# 02_PAB.net
KiCad netlist of a schematic drawn in Altium Designer
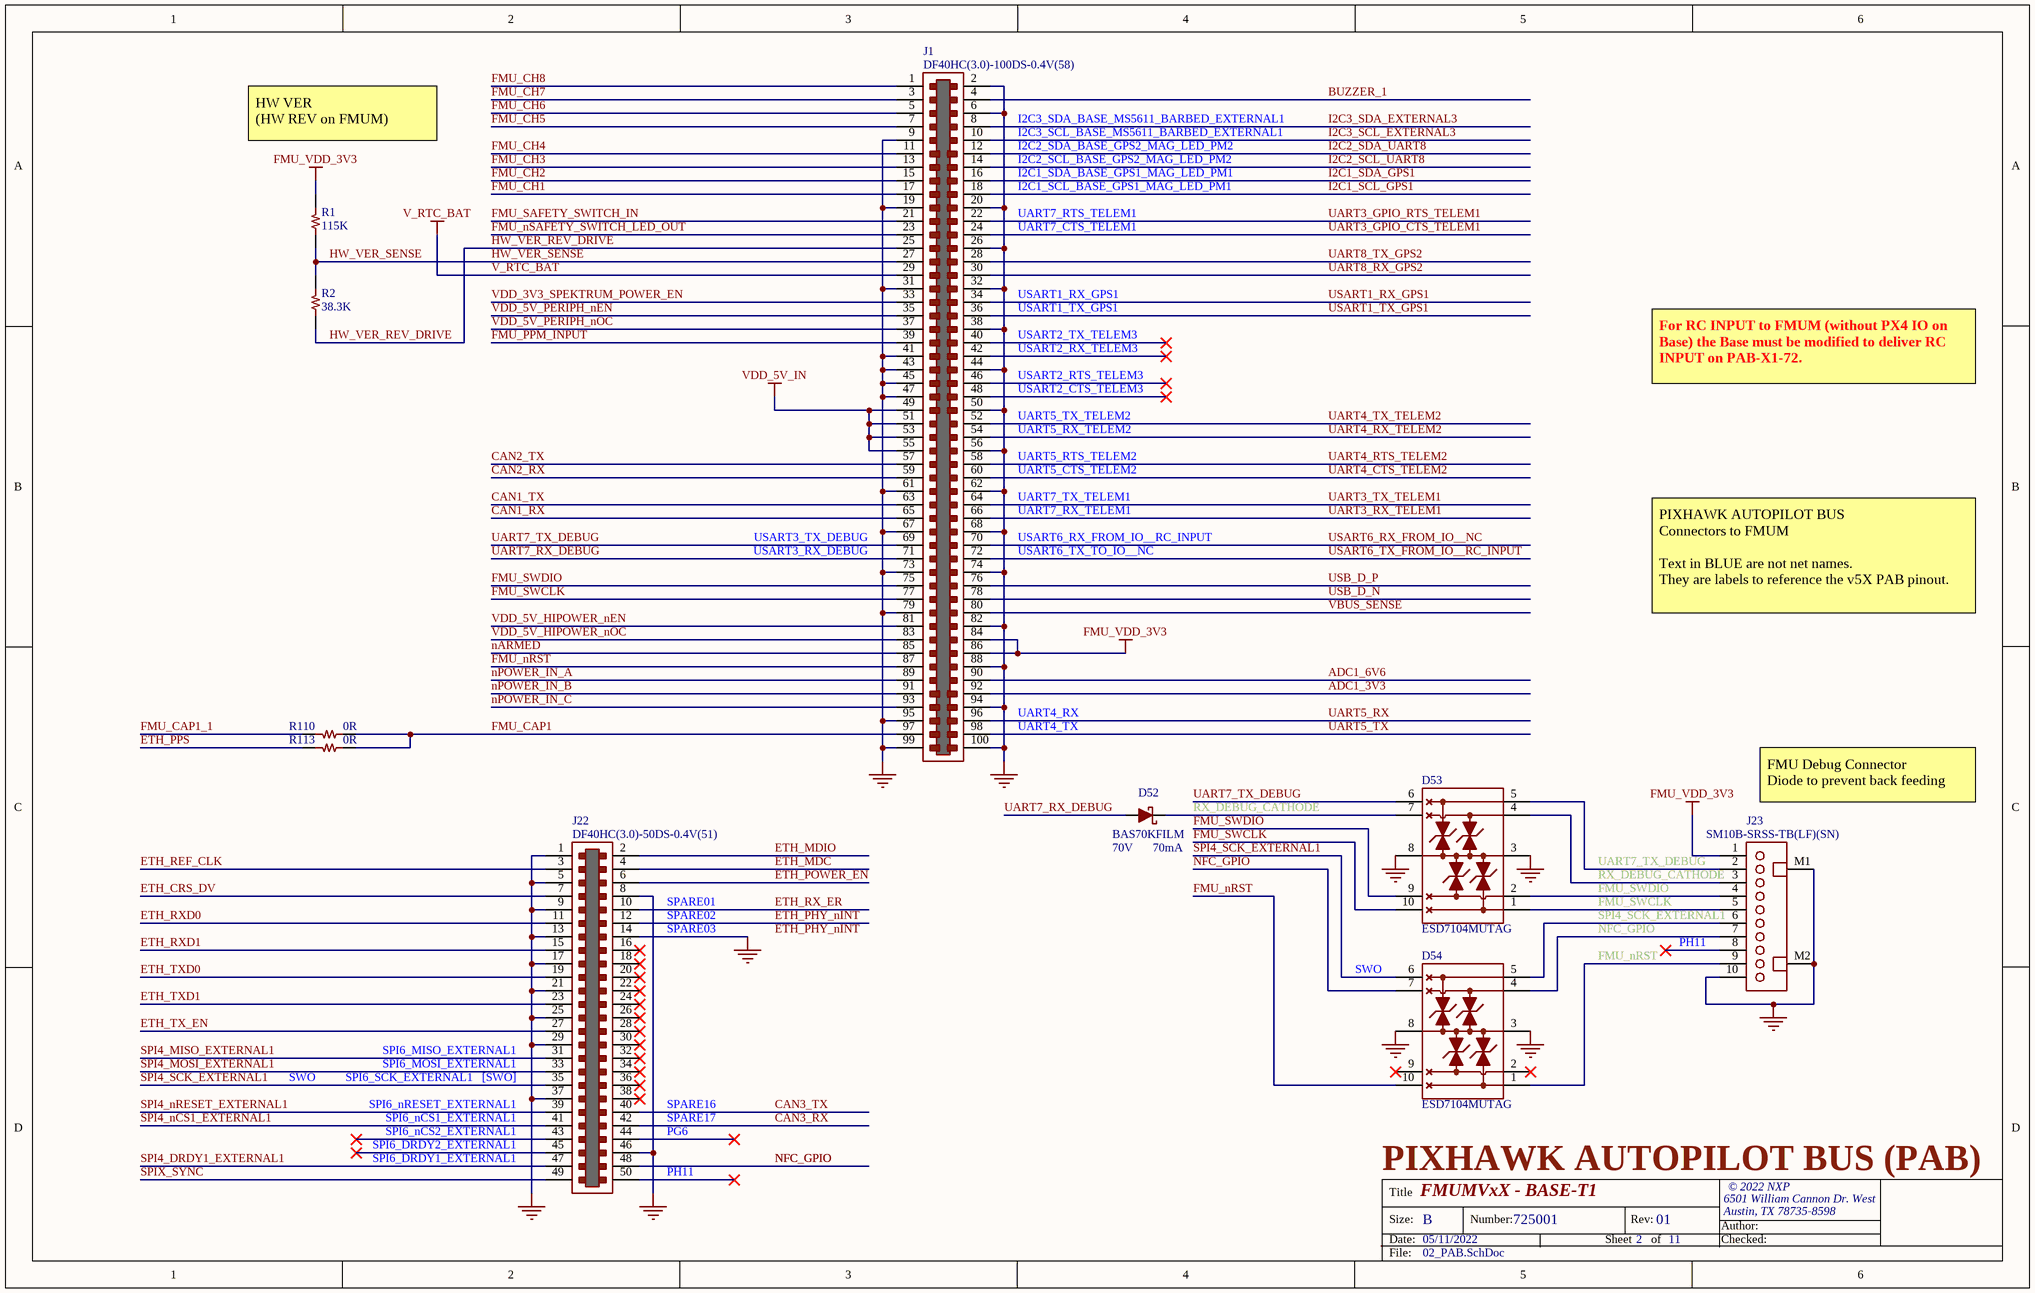
[diagram p0: 02_PAB.SchDoc]

(export (version "E")
  (design (tool "Eeschema 10.0.6"))
  (components
    (comp (ref "D52")
      (value "DIODE SCHOTTKY 70V 70MA SOD523")
      (footprint "SODFL120X80X70L30X30")
      (fields
        (field (name "MANUFACTURER") "STMicroelectronics")
        (field (name "MANUFACTURER PART NUMBER") "BAS70KFILM")
        (field (name "CURRENT") "70mA")
        (field (name "VOLTAGE") "70V")
      )
      (libsource (lib "NscDG_Integrated_Library") (part "DIODE_SCHOTTKY_BAS70_SOD523_SMT"))
    )
    (comp (ref "D53")
      (value "DIODE TVS BIDIRECTIONAL 5V 10V 10UDFN")
      (footprint "UDFN10P50_250X100X55L35X20N")
      (fields
        (field (name "MANUFACTURER") "ON Semiconductor")
        (field (name "MANUFACTURER PART NUMBER") "ESD7104MUTAG")
      )
      (libsource (lib "NscDG_Integrated_Library") (part "DIODE_TVS_4X_10UDFN"))
    )
    (comp (ref "D54")
      (value "DIODE TVS BIDIRECTIONAL 5V 10V 10UDFN")
      (footprint "UDFN10P50_250X100X55L35X20N")
      (fields
        (field (name "MANUFACTURER") "ON Semiconductor")
        (field (name "MANUFACTURER PART NUMBER") "ESD7104MUTAG")
      )
      (libsource (lib "NscDG_Integrated_Library") (part "DIODE_TVS_4X_10UDFN"))
    )
    (comp (ref "J1")
      (value "CONN RCPT 100POS 0.4MM SMD GOLD")
      (footprint "HIROSE_DF40HC3_0-100DS-0_4V51")
      (fields
        (field (name "MANUFACTURER") "Hirose Electric Co Ltd")
        (field (name "MANUFACTURER PART NUMBER") "DF40HC(3.0)-100DS-0.4V(58)")
      )
      (libsource (lib "NscDG_Integrated_Library") (part "CONN_RCPT_2X50_RECPT_0.4MM_SMD"))
    )
    (comp (ref "J22")
      (value "CONN RCPT 50POS 0.4MM SMD GOLD")
      (footprint "HIROSE_DF40C-50DS-0-4V51")
      (fields
        (field (name "MANUFACTURER") "Hirose Electric Co Ltd")
        (field (name "MANUFACTURER PART NUMBER") "DF40HC(3.0)-50DS-0.4V(51)")
      )
      (libsource (lib "NscDG_Integrated_Library") (part "CONN_RCPT_2X25_RECPT_0.4MM_SMD"))
    )
    (comp (ref "J23")
      (value "CONN HEADER SH 10POS SIDE 1MM SMT")
      (footprint "JST_SM10B-SRSS-TB")
      (fields
        (field (name "MANUFACTURER") "JST Sales America Inc.")
        (field (name "MANUFACTURER PART NUMBER") "SM10B-SRSS-TB(LF)(SN)")
      )
      (libsource (lib "NscDG_Integrated_Library") (part "CONN_JST_SH_10PIN_RA_SMT"))
    )
    (comp (ref "R1")
      (value "115K")
      (footprint "RESC100X50X40L25")
      (description "RES SMD 115K OHM 1% 1/16W 0402")
      (fields (field (name "TOLERANCE") "±1%") (field (name "MANUFACTURER") "Vishay Dale"))
      (libsource (lib "NscDG_Integrated_Library") (part "RES_115K_1%_1/16W_0402"))
    )
    (comp (ref "R2")
      (value "38.3K")
      (footprint "RESC100X50X40L25")
      (description "RES SMD 38.3K OHM 1% 1/16W 0402")
      (fields (field (name "TOLERANCE") "±1%") (field (name "MANUFACTURER") "Yageo"))
      (libsource (lib "NscDG_Integrated_Library") (part "RES_38.3K_1%_1/16W_0402"))
    )
    (comp (ref "R110")
      (value "0R")
      (footprint "RESC100X50X40L25")
      (description "RES SMD 0 OHM 1% 1/16W 0402")
      (fields (field (name "TOLERANCE") "±1%") (field (name "MANUFACTURER") "Yageo"))
      (libsource (lib "NscDG_Integrated_Library") (part "RES_0R_1%_1/16W_0402"))
    )
    (comp (ref "R113")
      (value "0R")
      (footprint "RESC100X50X40L25")
      (description "RES SMD 0 OHM 1% 1/16W 0402")
      (fields (field (name "TOLERANCE") "±1%") (field (name "MANUFACTURER") "Yageo"))
      (libsource (lib "NscDG_Integrated_Library") (part "RES_0R_1%_1/16W_0402"))
    )
  )
  (nets
    (net (code "1") (name "/ADC1_3V3") (class "Default")
      (node (ref "J1") (pin "92") (pinfunction "92_92") (pintype "passive"))
    )
    (net (code "2") (name "/ADC1_6V6") (class "Default")
      (node (ref "J1") (pin "90") (pinfunction "90_90") (pintype "passive"))
    )
    (net (code "3") (name "/BUZZER_1") (class "Default")
      (node (ref "J1") (pin "4") (pinfunction "4_4") (pintype "passive"))
    )
    (net (code "4") (name "/CAN1_RX") (class "Default")
      (node (ref "J1") (pin "65") (pinfunction "65_65") (pintype "passive"))
    )
    (net (code "5") (name "/CAN1_TX") (class "Default")
      (node (ref "J1") (pin "63") (pinfunction "63_63") (pintype "passive"))
    )
    (net (code "6") (name "/CAN2_RX") (class "Default")
      (node (ref "J1") (pin "59") (pinfunction "59_59") (pintype "passive"))
    )
    (net (code "7") (name "/CAN2_TX") (class "Default")
      (node (ref "J1") (pin "57") (pinfunction "57_57") (pintype "passive"))
    )
    (net (code "8") (name "/CAN3_RX") (class "Default")
      (node (ref "J22") (pin "42") (pinfunction "42_42") (pintype "passive"))
    )
    (net (code "9") (name "/CAN3_TX") (class "Default")
      (node (ref "J22") (pin "40") (pinfunction "40_40") (pintype "passive"))
    )
    (net (code "10") (name "/ETH_CRS_DV") (class "Default")
      (node (ref "J22") (pin "7") (pinfunction "7_7") (pintype "passive"))
    )
    (net (code "11") (name "/ETH_MDC") (class "Default")
      (node (ref "J22") (pin "4") (pinfunction "4_4") (pintype "passive"))
    )
    (net (code "12") (name "/ETH_MDIO") (class "Default")
      (node (ref "J22") (pin "2") (pinfunction "2_2") (pintype "passive"))
    )
    (net (code "13") (name "/ETH_PHY_nINT") (class "Default")
      (node (ref "J22") (pin "12") (pinfunction "12_12") (pintype "passive"))
    )
    (net (code "14") (name "/ETH_POWER_EN") (class "Default")
      (node (ref "J22") (pin "6") (pinfunction "6_6") (pintype "passive"))
    )
    (net (code "15") (name "/ETH_PPS") (class "Default")
      (node (ref "R113") (pin "1") (pinfunction "1_1") (pintype "passive"))
    )
    (net (code "16") (name "/ETH_REF_CLK") (class "Default")
      (node (ref "J22") (pin "3") (pinfunction "3_3") (pintype "passive"))
    )
    (net (code "17") (name "/ETH_RXD0") (class "Default")
      (node (ref "J22") (pin "11") (pinfunction "11_11") (pintype "passive"))
    )
    (net (code "18") (name "/ETH_RXD1") (class "Default")
      (node (ref "J22") (pin "15") (pinfunction "15_15") (pintype "passive"))
    )
    (net (code "19") (name "/ETH_RX_ER") (class "Default")
      (node (ref "J22") (pin "10") (pinfunction "10_10") (pintype "passive"))
    )
    (net (code "20") (name "/ETH_TXD0") (class "Default")
      (node (ref "J22") (pin "19") (pinfunction "19_19") (pintype "passive"))
    )
    (net (code "21") (name "/ETH_TXD1") (class "Default")
      (node (ref "J22") (pin "23") (pinfunction "23_23") (pintype "passive"))
    )
    (net (code "22") (name "/ETH_TX_EN") (class "Default")
      (node (ref "J22") (pin "27") (pinfunction "27_27") (pintype "passive"))
    )
    (net (code "23") (name "/FMU_CAP1") (class "Default")
      (node (ref "J1") (pin "97") (pinfunction "97_97") (pintype "passive"))
      (node (ref "R110") (pin "2") (pinfunction "2_2") (pintype "passive"))
      (node (ref "R113") (pin "2") (pinfunction "2_2") (pintype "passive"))
    )
    (net (code "24") (name "/FMU_CAP1_1") (class "Default")
      (node (ref "R110") (pin "1") (pinfunction "1_1") (pintype "passive"))
    )
    (net (code "25") (name "/FMU_CH1") (class "Default")
      (node (ref "J1") (pin "17") (pinfunction "17_17") (pintype "passive"))
    )
    (net (code "26") (name "/FMU_CH2") (class "Default")
      (node (ref "J1") (pin "15") (pinfunction "15_15") (pintype "passive"))
    )
    (net (code "27") (name "/FMU_CH3") (class "Default")
      (node (ref "J1") (pin "13") (pinfunction "13_13") (pintype "passive"))
    )
    (net (code "28") (name "/FMU_CH4") (class "Default")
      (node (ref "J1") (pin "11") (pinfunction "11_11") (pintype "passive"))
    )
    (net (code "29") (name "/FMU_CH5") (class "Default")
      (node (ref "J1") (pin "7") (pinfunction "7_7") (pintype "passive"))
    )
    (net (code "30") (name "/FMU_CH6") (class "Default")
      (node (ref "J1") (pin "5") (pinfunction "5_5") (pintype "passive"))
    )
    (net (code "31") (name "/FMU_CH7") (class "Default")
      (node (ref "J1") (pin "3") (pinfunction "3_3") (pintype "passive"))
    )
    (net (code "32") (name "/FMU_CH8") (class "Default")
      (node (ref "J1") (pin "1") (pinfunction "1_1") (pintype "passive"))
    )
    (net (code "33") (name "/FMU_PPM_INPUT") (class "Default")
      (node (ref "J1") (pin "39") (pinfunction "39_39") (pintype "passive"))
    )
    (net (code "34") (name "/FMU_SAFETY_SWITCH_IN") (class "Default")
      (node (ref "J1") (pin "21") (pinfunction "21_21") (pintype "passive"))
    )
    (net (code "35") (name "/FMU_SWCLK") (class "Default")
      (node (ref "D53") (pin "1") (pinfunction "1_1") (pintype "passive"))
      (node (ref "D53") (pin "10") (pinfunction "NC_10") (pintype "passive"))
      (node (ref "J1") (pin "77") (pinfunction "77_77") (pintype "passive"))
      (node (ref "J23") (pin "5") (pinfunction "5_5") (pintype "passive"))
    )
    (net (code "36") (name "/FMU_SWDIO") (class "Default")
      (node (ref "D53") (pin "2") (pinfunction "2_2") (pintype "passive"))
      (node (ref "D53") (pin "9") (pinfunction "NC_9") (pintype "passive"))
      (node (ref "J1") (pin "75") (pinfunction "75_75") (pintype "passive"))
      (node (ref "J23") (pin "4") (pinfunction "4_4") (pintype "passive"))
    )
    (net (code "37") (name "/FMU_nRST") (class "Default")
      (node (ref "D54") (pin "1") (pinfunction "1_1") (pintype "passive"))
      (node (ref "D54") (pin "10") (pinfunction "NC_10") (pintype "passive"))
      (node (ref "J1") (pin "87") (pinfunction "87_87") (pintype "passive"))
      (node (ref "J23") (pin "9") (pinfunction "9_9") (pintype "passive"))
    )
    (net (code "38") (name "/FMU_nSAFETY_SWITCH_LED_OUT") (class "Default")
      (node (ref "J1") (pin "23") (pinfunction "23_23") (pintype "passive"))
    )
    (net (code "39") (name "/HW_VER_REV_DRIVE") (class "Default")
      (node (ref "J1") (pin "25") (pinfunction "25_25") (pintype "passive"))
      (node (ref "R2") (pin "2") (pinfunction "2_2") (pintype "passive"))
    )
    (net (code "40") (name "/HW_VER_SENSE") (class "Default")
      (node (ref "J1") (pin "27") (pinfunction "27_27") (pintype "passive"))
      (node (ref "R1") (pin "2") (pinfunction "2_2") (pintype "passive"))
      (node (ref "R2") (pin "1") (pinfunction "1_1") (pintype "passive"))
    )
    (net (code "41") (name "/I2C1_SCL_GPS1") (class "Default")
      (node (ref "J1") (pin "18") (pinfunction "18_18") (pintype "passive"))
    )
    (net (code "42") (name "/I2C1_SDA_GPS1") (class "Default")
      (node (ref "J1") (pin "16") (pinfunction "16_16") (pintype "passive"))
    )
    (net (code "43") (name "/I2C2_SCL_UART8") (class "Default")
      (node (ref "J1") (pin "14") (pinfunction "14_14") (pintype "passive"))
    )
    (net (code "44") (name "/I2C2_SDA_UART8") (class "Default")
      (node (ref "J1") (pin "12") (pinfunction "12_12") (pintype "passive"))
    )
    (net (code "45") (name "/I2C3_SCL_EXTERNAL3") (class "Default")
      (node (ref "J1") (pin "10") (pinfunction "10_10") (pintype "passive"))
    )
    (net (code "46") (name "/I2C3_SDA_EXTERNAL3") (class "Default")
      (node (ref "J1") (pin "8") (pinfunction "8_8") (pintype "passive"))
    )
    (net (code "47") (name "/NFC_GPIO") (class "Default")
      (node (ref "D54") (pin "4") (pinfunction "4_4") (pintype "passive"))
      (node (ref "D54") (pin "7") (pinfunction "NC_7") (pintype "passive"))
      (node (ref "J22") (pin "48") (pinfunction "48_48") (pintype "passive"))
      (node (ref "J23") (pin "7") (pinfunction "7_7") (pintype "passive"))
    )
    (net (code "48") (name "/RX_DEBUG_CATHODE") (class "Default")
      (node (ref "D52") (pin "C") (pinfunction "C_C") (pintype "passive"))
      (node (ref "D53") (pin "4") (pinfunction "4_4") (pintype "passive"))
      (node (ref "D53") (pin "7") (pinfunction "NC_7") (pintype "passive"))
      (node (ref "J23") (pin "3") (pinfunction "3_3") (pintype "passive"))
    )
    (net (code "49") (name "/SPI4_DRDY1_EXTERNAL1") (class "Default")
      (node (ref "J22") (pin "47") (pinfunction "47_47") (pintype "passive"))
    )
    (net (code "50") (name "/SPI4_MISO_EXTERNAL1") (class "Default")
      (node (ref "J22") (pin "31") (pinfunction "31_31") (pintype "passive"))
    )
    (net (code "51") (name "/SPI4_MOSI_EXTERNAL1") (class "Default")
      (node (ref "J22") (pin "33") (pinfunction "33_33") (pintype "passive"))
    )
    (net (code "52") (name "/SPI4_SCK_EXTERNAL1") (class "Default")
      (node (ref "D54") (pin "5") (pinfunction "5_5") (pintype "passive"))
      (node (ref "D54") (pin "6") (pinfunction "NC_6") (pintype "passive"))
      (node (ref "J22") (pin "35") (pinfunction "35_35") (pintype "passive"))
      (node (ref "J23") (pin "6") (pinfunction "6_6") (pintype "passive"))
    )
    (net (code "53") (name "/SPI4_nCS1_EXTERNAL1") (class "Default")
      (node (ref "J22") (pin "41") (pinfunction "41_41") (pintype "passive"))
    )
    (net (code "54") (name "/SPI4_nRESET_EXTERNAL1") (class "Default")
      (node (ref "J22") (pin "39") (pinfunction "39_39") (pintype "passive"))
    )
    (net (code "55") (name "/SPIX_SYNC") (class "Default")
      (node (ref "J22") (pin "49") (pinfunction "49_49") (pintype "passive"))
    )
    (net (code "56") (name "/UART3_GPIO_CTS_TELEM1") (class "Default")
      (node (ref "J1") (pin "24") (pinfunction "24_24") (pintype "passive"))
    )
    (net (code "57") (name "/UART3_GPIO_RTS_TELEM1") (class "Default")
      (node (ref "J1") (pin "22") (pinfunction "22_22") (pintype "passive"))
    )
    (net (code "58") (name "/UART3_RX_TELEM1") (class "Default")
      (node (ref "J1") (pin "66") (pinfunction "66_66") (pintype "passive"))
    )
    (net (code "59") (name "/UART3_TX_TELEM1") (class "Default")
      (node (ref "J1") (pin "64") (pinfunction "64_64") (pintype "passive"))
    )
    (net (code "60") (name "/UART4_CTS_TELEM2") (class "Default")
      (node (ref "J1") (pin "60") (pinfunction "60_60") (pintype "passive"))
    )
    (net (code "61") (name "/UART4_RTS_TELEM2") (class "Default")
      (node (ref "J1") (pin "58") (pinfunction "58_58") (pintype "passive"))
    )
    (net (code "62") (name "/UART4_RX_TELEM2") (class "Default")
      (node (ref "J1") (pin "54") (pinfunction "54_54") (pintype "passive"))
    )
    (net (code "63") (name "/UART4_TX_TELEM2") (class "Default")
      (node (ref "J1") (pin "52") (pinfunction "52_52") (pintype "passive"))
    )
    (net (code "64") (name "/UART5_RX") (class "Default")
      (node (ref "J1") (pin "96") (pinfunction "96_96") (pintype "passive"))
    )
    (net (code "65") (name "/UART5_TX") (class "Default")
      (node (ref "J1") (pin "98") (pinfunction "98_98") (pintype "passive"))
    )
    (net (code "66") (name "/UART7_RX_DEBUG") (class "Default")
      (node (ref "D52") (pin "A") (pinfunction "A_A") (pintype "passive"))
      (node (ref "J1") (pin "71") (pinfunction "71_71") (pintype "passive"))
    )
    (net (code "67") (name "/UART7_TX_DEBUG") (class "Default")
      (node (ref "D53") (pin "5") (pinfunction "5_5") (pintype "passive"))
      (node (ref "D53") (pin "6") (pinfunction "NC_6") (pintype "passive"))
      (node (ref "J1") (pin "69") (pinfunction "69_69") (pintype "passive"))
      (node (ref "J23") (pin "2") (pinfunction "2_2") (pintype "passive"))
    )
    (net (code "68") (name "/UART8_RX_GPS2") (class "Default")
      (node (ref "J1") (pin "30") (pinfunction "30_30") (pintype "passive"))
    )
    (net (code "69") (name "/UART8_TX_GPS2") (class "Default")
      (node (ref "J1") (pin "28") (pinfunction "28_28") (pintype "passive"))
    )
    (net (code "70") (name "/USART1_RX_GPS1") (class "Default")
      (node (ref "J1") (pin "34") (pinfunction "34_34") (pintype "passive"))
    )
    (net (code "71") (name "/USART1_TX_GPS1") (class "Default")
      (node (ref "J1") (pin "36") (pinfunction "36_36") (pintype "passive"))
    )
    (net (code "72") (name "/USART6_RX_FROM_IO__NC") (class "Default")
      (node (ref "J1") (pin "70") (pinfunction "70_70") (pintype "passive"))
    )
    (net (code "73") (name "/USART6_TX_FROM_IO__RC_INPUT") (class "Default")
      (node (ref "J1") (pin "72") (pinfunction "72_72") (pintype "passive"))
    )
    (net (code "74") (name "/USB_D_N") (class "Default")
      (node (ref "J1") (pin "78") (pinfunction "78_78") (pintype "passive"))
    )
    (net (code "75") (name "/USB_D_P") (class "Default")
      (node (ref "J1") (pin "76") (pinfunction "76_76") (pintype "passive"))
    )
    (net (code "76") (name "/VBUS_SENSE") (class "Default")
      (node (ref "J1") (pin "80") (pinfunction "80_80") (pintype "passive"))
    )
    (net (code "77") (name "/VDD_3V3_SPEKTRUM_POWER_EN") (class "Default")
      (node (ref "J1") (pin "33") (pinfunction "33_33") (pintype "passive"))
    )
    (net (code "78") (name "/VDD_5V_HIPOWER_nEN") (class "Default")
      (node (ref "J1") (pin "81") (pinfunction "81_81") (pintype "passive"))
    )
    (net (code "79") (name "/VDD_5V_HIPOWER_nOC") (class "Default")
      (node (ref "J1") (pin "83") (pinfunction "83_83") (pintype "passive"))
    )
    (net (code "80") (name "/VDD_5V_PERIPH_nEN") (class "Default")
      (node (ref "J1") (pin "35") (pinfunction "35_35") (pintype "passive"))
    )
    (net (code "81") (name "/VDD_5V_PERIPH_nOC") (class "Default")
      (node (ref "J1") (pin "37") (pinfunction "37_37") (pintype "passive"))
    )
    (net (code "82") (name "/nARMED") (class "Default")
      (node (ref "J1") (pin "85") (pinfunction "85_85") (pintype "passive"))
    )
    (net (code "83") (name "/nPOWER_IN_A") (class "Default")
      (node (ref "J1") (pin "89") (pinfunction "89_89") (pintype "passive"))
    )
    (net (code "84") (name "/nPOWER_IN_B") (class "Default")
      (node (ref "J1") (pin "91") (pinfunction "91_91") (pintype "passive"))
    )
    (net (code "85") (name "/nPOWER_IN_C") (class "Default")
      (node (ref "J1") (pin "93") (pinfunction "93_93") (pintype "passive"))
    )
    (net (code "86") (name "FMU_VDD_3V3") (class "Default")
      (node (ref "J1") (pin "84") (pinfunction "84_84") (pintype "passive"))
      (node (ref "J1") (pin "86") (pinfunction "86_86") (pintype "passive"))
      (node (ref "J23") (pin "1") (pinfunction "1_1") (pintype "passive"))
      (node (ref "R1") (pin "1") (pinfunction "1_1") (pintype "passive"))
    )
    (net (code "87") (name "GND") (class "Default")
      (node (ref "D53") (pin "3") (pinfunction "GND_3") (pintype "passive"))
      (node (ref "D53") (pin "8") (pinfunction "GND_8") (pintype "passive"))
      (node (ref "D54") (pin "3") (pinfunction "GND_3") (pintype "passive"))
      (node (ref "D54") (pin "8") (pinfunction "GND_8") (pintype "passive"))
      (node (ref "J1") (pin "100") (pinfunction "100_100") (pintype "passive"))
      (node (ref "J1") (pin "19") (pinfunction "19_19") (pintype "passive"))
      (node (ref "J1") (pin "2") (pinfunction "2_2") (pintype "passive"))
      (node (ref "J1") (pin "20") (pinfunction "20_20") (pintype "passive"))
      (node (ref "J1") (pin "26") (pinfunction "26_26") (pintype "passive"))
      (node (ref "J1") (pin "31") (pinfunction "31_31") (pintype "passive"))
      (node (ref "J1") (pin "32") (pinfunction "32_32") (pintype "passive"))
      (node (ref "J1") (pin "38") (pinfunction "38_38") (pintype "passive"))
      (node (ref "J1") (pin "41") (pinfunction "41_41") (pintype "passive"))
      (node (ref "J1") (pin "43") (pinfunction "43_43") (pintype "passive"))
      (node (ref "J1") (pin "44") (pinfunction "44_44") (pintype "passive"))
      (node (ref "J1") (pin "45") (pinfunction "45_45") (pintype "passive"))
      (node (ref "J1") (pin "47") (pinfunction "47_47") (pintype "passive"))
      (node (ref "J1") (pin "50") (pinfunction "50_50") (pintype "passive"))
      (node (ref "J1") (pin "56") (pinfunction "56_56") (pintype "passive"))
      (node (ref "J1") (pin "6") (pinfunction "6_6") (pintype "passive"))
      (node (ref "J1") (pin "61") (pinfunction "61_61") (pintype "passive"))
      (node (ref "J1") (pin "62") (pinfunction "62_62") (pintype "passive"))
      (node (ref "J1") (pin "67") (pinfunction "67_67") (pintype "passive"))
      (node (ref "J1") (pin "68") (pinfunction "68_68") (pintype "passive"))
      (node (ref "J1") (pin "73") (pinfunction "73_73") (pintype "passive"))
      (node (ref "J1") (pin "74") (pinfunction "74_74") (pintype "passive"))
      (node (ref "J1") (pin "79") (pinfunction "79_79") (pintype "passive"))
      (node (ref "J1") (pin "82") (pinfunction "82_82") (pintype "passive"))
      (node (ref "J1") (pin "88") (pinfunction "88_88") (pintype "passive"))
      (node (ref "J1") (pin "9") (pinfunction "9_9") (pintype "passive"))
      (node (ref "J1") (pin "94") (pinfunction "94_94") (pintype "passive"))
      (node (ref "J1") (pin "95") (pinfunction "95_95") (pintype "passive"))
      (node (ref "J1") (pin "99") (pinfunction "99_99") (pintype "passive"))
      (node (ref "J22") (pin "1") (pinfunction "1_1") (pintype "passive"))
      (node (ref "J22") (pin "13") (pinfunction "13_13") (pintype "passive"))
      (node (ref "J22") (pin "14") (pinfunction "14_14") (pintype "passive"))
      (node (ref "J22") (pin "17") (pinfunction "17_17") (pintype "passive"))
      (node (ref "J22") (pin "21") (pinfunction "21_21") (pintype "passive"))
      (node (ref "J22") (pin "25") (pinfunction "25_25") (pintype "passive"))
      (node (ref "J22") (pin "29") (pinfunction "29_29") (pintype "passive"))
      (node (ref "J22") (pin "37") (pinfunction "37_37") (pintype "passive"))
      (node (ref "J22") (pin "46") (pinfunction "46_46") (pintype "passive"))
      (node (ref "J22") (pin "5") (pinfunction "5_5") (pintype "passive"))
      (node (ref "J22") (pin "8") (pinfunction "8_8") (pintype "passive"))
      (node (ref "J22") (pin "9") (pinfunction "9_9") (pintype "passive"))
      (node (ref "J23") (pin "10") (pinfunction "10_10") (pintype "passive"))
      (node (ref "J23") (pin "M1") (pinfunction "M1_M1") (pintype "passive"))
      (node (ref "J23") (pin "M2") (pinfunction "M2_M2") (pintype "passive"))
    )
    (net (code "88") (name "VDD_5V_IN") (class "Default")
      (node (ref "J1") (pin "49") (pinfunction "49_49") (pintype "passive"))
      (node (ref "J1") (pin "51") (pinfunction "51_51") (pintype "passive"))
      (node (ref "J1") (pin "53") (pinfunction "53_53") (pintype "passive"))
      (node (ref "J1") (pin "55") (pinfunction "55_55") (pintype "passive"))
    )
    (net (code "89") (name "V_RTC_BAT") (class "Default")
      (node (ref "J1") (pin "29") (pinfunction "29_29") (pintype "passive"))
    )
    (net (code "90") (name "unconnected-(D54-NC-Pad9)") (class "Default")
      (node (ref "D54") (pin "9") (pinfunction "NC_9") (pintype "passive+no_connect"))
    )
    (net (code "91") (name "unconnected-(D54-Pad2)") (class "Default")
      (node (ref "D54") (pin "2") (pinfunction "2_2") (pintype "passive+no_connect"))
    )
    (net (code "92") (name "unconnected-(J1-Pad40)") (class "Default")
      (node (ref "J1") (pin "40") (pinfunction "40_40") (pintype "passive+no_connect"))
    )
    (net (code "93") (name "unconnected-(J1-Pad42)") (class "Default")
      (node (ref "J1") (pin "42") (pinfunction "42_42") (pintype "passive+no_connect"))
    )
    (net (code "94") (name "unconnected-(J1-Pad46)") (class "Default")
      (node (ref "J1") (pin "46") (pinfunction "46_46") (pintype "passive+no_connect"))
    )
    (net (code "95") (name "unconnected-(J1-Pad48)") (class "Default")
      (node (ref "J1") (pin "48") (pinfunction "48_48") (pintype "passive+no_connect"))
    )
    (net (code "96") (name "unconnected-(J22-Pad16)") (class "Default")
      (node (ref "J22") (pin "16") (pinfunction "16_16") (pintype "passive+no_connect"))
    )
    (net (code "97") (name "unconnected-(J22-Pad18)") (class "Default")
      (node (ref "J22") (pin "18") (pinfunction "18_18") (pintype "passive+no_connect"))
    )
    (net (code "98") (name "unconnected-(J22-Pad20)") (class "Default")
      (node (ref "J22") (pin "20") (pinfunction "20_20") (pintype "passive+no_connect"))
    )
    (net (code "99") (name "unconnected-(J22-Pad22)") (class "Default")
      (node (ref "J22") (pin "22") (pinfunction "22_22") (pintype "passive+no_connect"))
    )
    (net (code "100") (name "unconnected-(J22-Pad24)") (class "Default")
      (node (ref "J22") (pin "24") (pinfunction "24_24") (pintype "passive+no_connect"))
    )
    (net (code "101") (name "unconnected-(J22-Pad26)") (class "Default")
      (node (ref "J22") (pin "26") (pinfunction "26_26") (pintype "passive+no_connect"))
    )
    (net (code "102") (name "unconnected-(J22-Pad28)") (class "Default")
      (node (ref "J22") (pin "28") (pinfunction "28_28") (pintype "passive+no_connect"))
    )
    (net (code "103") (name "unconnected-(J22-Pad30)") (class "Default")
      (node (ref "J22") (pin "30") (pinfunction "30_30") (pintype "passive+no_connect"))
    )
    (net (code "104") (name "unconnected-(J22-Pad32)") (class "Default")
      (node (ref "J22") (pin "32") (pinfunction "32_32") (pintype "passive+no_connect"))
    )
    (net (code "105") (name "unconnected-(J22-Pad34)") (class "Default")
      (node (ref "J22") (pin "34") (pinfunction "34_34") (pintype "passive+no_connect"))
    )
    (net (code "106") (name "unconnected-(J22-Pad36)") (class "Default")
      (node (ref "J22") (pin "36") (pinfunction "36_36") (pintype "passive+no_connect"))
    )
    (net (code "107") (name "unconnected-(J22-Pad38)") (class "Default")
      (node (ref "J22") (pin "38") (pinfunction "38_38") (pintype "passive+no_connect"))
    )
    (net (code "108") (name "unconnected-(J22-Pad43)") (class "Default")
      (node (ref "J22") (pin "43") (pinfunction "43_43") (pintype "passive+no_connect"))
    )
    (net (code "109") (name "unconnected-(J22-Pad44)") (class "Default")
      (node (ref "J22") (pin "44") (pinfunction "44_44") (pintype "passive+no_connect"))
    )
    (net (code "110") (name "unconnected-(J22-Pad45)") (class "Default")
      (node (ref "J22") (pin "45") (pinfunction "45_45") (pintype "passive+no_connect"))
    )
    (net (code "111") (name "unconnected-(J22-Pad50)") (class "Default")
      (node (ref "J22") (pin "50") (pinfunction "50_50") (pintype "passive+no_connect"))
    )
    (net (code "112") (name "unconnected-(J23-Pad8)") (class "Default")
      (node (ref "J23") (pin "8") (pinfunction "8_8") (pintype "passive+no_connect"))
    )
  )
)
